# SoundChip.net
KiCad netlist of a schematic drawn in Altium Designer
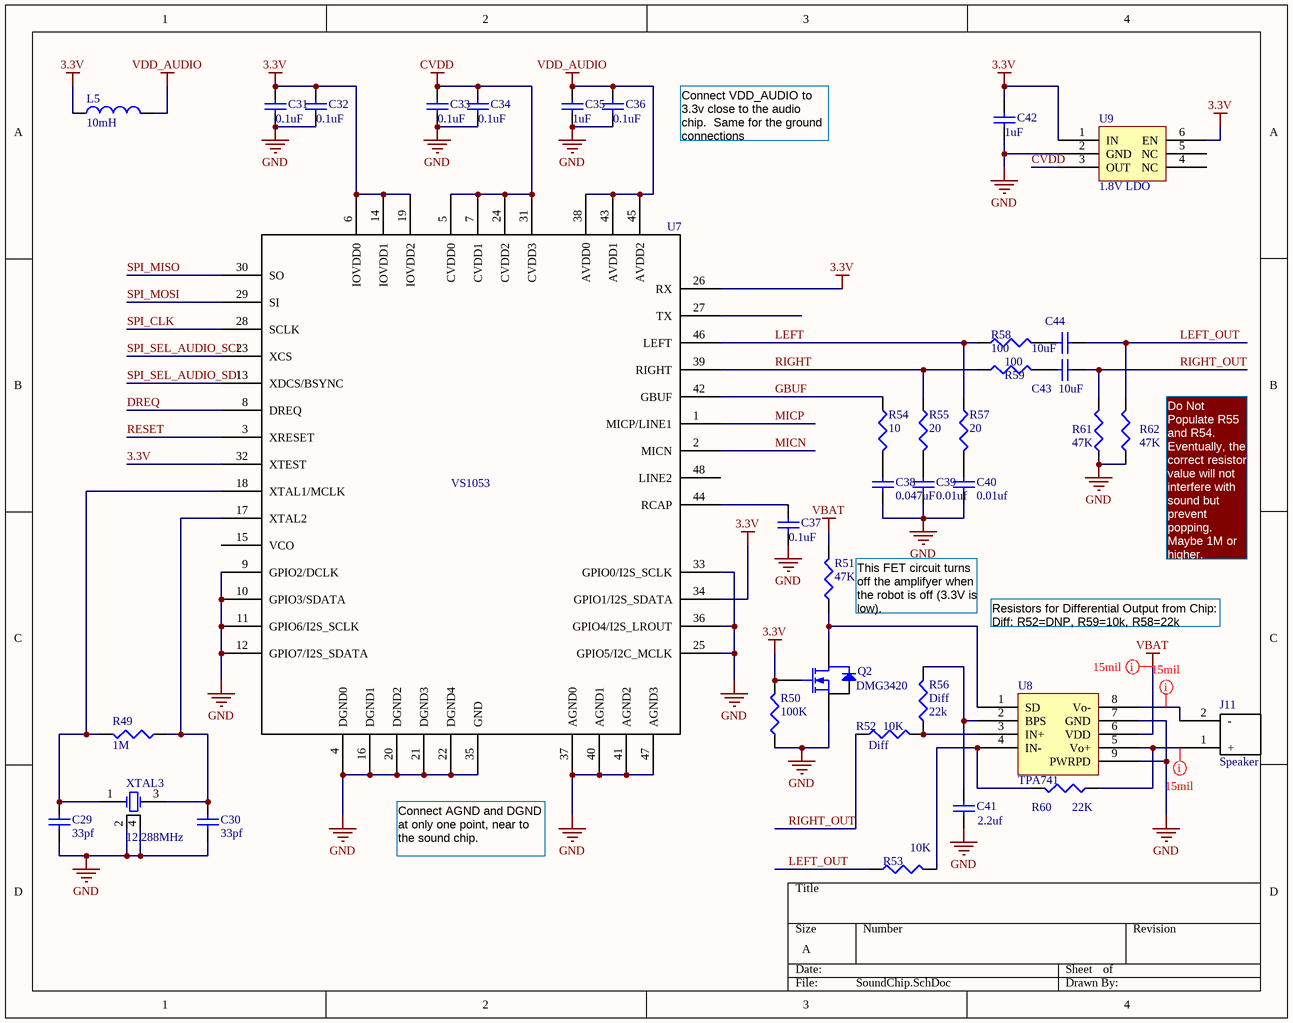
[diagram p0: SoundChip.SchDoc]

(export (version "E")
  (design (tool "Eeschema 10.0.6"))
  (components
    (comp (ref "C29")
      (value "33pf")
      (footprint "CAPC1005L")
      (description "Capacitor (Semiconductor SIM Model)")
      (fields (field (name "Comment") "Cap Semi") (field (name "PUBLISHER") "Altium Limited"))
      (libsource (lib "Miscellaneous Devices") (part "Cap Semi"))
    )
    (comp (ref "C30")
      (value "33pf")
      (footprint "CAPC1005L")
      (description "Capacitor (Semiconductor SIM Model)")
      (fields (field (name "Comment") "Cap Semi") (field (name "PUBLISHER") "Altium Limited"))
      (libsource (lib "Miscellaneous Devices") (part "Cap Semi"))
    )
    (comp (ref "C31")
      (value "0.1uF")
      (footprint "CAPC1005L")
      (description "Capacitor (Semiconductor SIM Model)")
      (fields (field (name "Comment") "Cap Semi") (field (name "PUBLISHER") "Altium Limited"))
      (libsource (lib "Miscellaneous Devices") (part "Cap Semi"))
    )
    (comp (ref "C32")
      (value "0.1uF")
      (footprint "CAPC1005L")
      (description "Capacitor (Semiconductor SIM Model)")
      (fields (field (name "Comment") "Cap Semi") (field (name "PUBLISHER") "Altium Limited"))
      (libsource (lib "Miscellaneous Devices") (part "Cap Semi"))
    )
    (comp (ref "C33")
      (value "0.1uF")
      (footprint "CAPC1005L")
      (description "Capacitor (Semiconductor SIM Model)")
      (fields (field (name "Comment") "Cap Semi") (field (name "PUBLISHER") "Altium Limited"))
      (libsource (lib "Miscellaneous Devices") (part "Cap Semi"))
    )
    (comp (ref "C34")
      (value "0.1uF")
      (footprint "CAPC1005L")
      (description "Capacitor (Semiconductor SIM Model)")
      (fields (field (name "Comment") "Cap Semi") (field (name "PUBLISHER") "Altium Limited"))
      (libsource (lib "Miscellaneous Devices") (part "Cap Semi"))
    )
    (comp (ref "C35")
      (value "1uF")
      (footprint "CAPC1608L")
      (description "Capacitor (Semiconductor SIM Model)")
      (fields (field (name "Comment") "Cap Semi") (field (name "PUBLISHER") "Altium Limited"))
      (libsource (lib "Miscellaneous Devices") (part "Cap Semi"))
    )
    (comp (ref "C36")
      (value "0.1uF")
      (footprint "CAPC1005L")
      (description "Capacitor (Semiconductor SIM Model)")
      (fields (field (name "Comment") "Cap Semi") (field (name "PUBLISHER") "Altium Limited"))
      (libsource (lib "Miscellaneous Devices") (part "Cap Semi"))
    )
    (comp (ref "C37")
      (value "0.1uF")
      (footprint "CAPC1005L")
      (description "Capacitor (Semiconductor SIM Model)")
      (fields (field (name "Comment") "Cap Semi") (field (name "PUBLISHER") "Altium Limited"))
      (libsource (lib "Miscellaneous Devices") (part "Cap Semi"))
    )
    (comp (ref "C38")
      (value "0.047uF")
      (footprint "CAPC1005L")
      (description "Capacitor (Semiconductor SIM Model)")
      (fields (field (name "Comment") "Cap Semi") (field (name "PUBLISHER") "Altium Limited"))
      (libsource (lib "Miscellaneous Devices") (part "Cap Semi"))
    )
    (comp (ref "C39")
      (value "0.01uf")
      (footprint "CAPC1005L")
      (description "Capacitor (Semiconductor SIM Model)")
      (fields (field (name "Comment") "Cap Semi") (field (name "PUBLISHER") "Altium Limited"))
      (libsource (lib "Miscellaneous Devices") (part "Cap Semi"))
    )
    (comp (ref "C40")
      (value "0.01uf")
      (footprint "CAPC1005L")
      (description "Capacitor (Semiconductor SIM Model)")
      (fields (field (name "Comment") "Cap Semi") (field (name "PUBLISHER") "Altium Limited"))
      (libsource (lib "Miscellaneous Devices") (part "Cap Semi"))
    )
    (comp (ref "C41")
      (value "2.2uf")
      (footprint "J1-0603")
      (description "Capacitor (Semiconductor SIM Model)")
      (fields (field (name "Comment") "Cap Semi") (field (name "PUBLISHER") "Altium Limited"))
      (libsource (lib "Miscellaneous Devices") (part "Cap Semi"))
    )
    (comp (ref "C42")
      (value "1uF")
      (footprint "CAPC1608L")
      (description "Capacitor (Semiconductor SIM Model)")
      (fields (field (name "Comment") "Cap Semi") (field (name "PUBLISHER") "Altium Limited"))
      (libsource (lib "Miscellaneous Devices") (part "Cap Semi"))
    )
    (comp (ref "C43")
      (value "10uF")
      (footprint "CAPC1608L")
      (description "Capacitor (Semiconductor SIM Model)")
      (fields (field (name "Comment") "Cap Semi") (field (name "PUBLISHER") "Altium Limited"))
      (libsource (lib "Miscellaneous Devices") (part "Cap Semi"))
    )
    (comp (ref "C44")
      (value "10uF")
      (footprint "CAPC1608L")
      (description "Capacitor (Semiconductor SIM Model)")
      (fields (field (name "Comment") "Cap Semi") (field (name "PUBLISHER") "Altium Limited"))
      (libsource (lib "Miscellaneous Devices") (part "Cap Semi"))
    )
    (comp (ref "J11")
      (value "Speaker")
      (footprint "BatteryConnJST")
      (libsource (lib "mrone") (part "BatteryConnJST"))
    )
    (comp (ref "L5")
      (value "10mH")
      (footprint "INDC2012L")
      (description "Inductor")
      (fields (field (name "PUBLISHER") "Altium Limited"))
      (libsource (lib "Miscellaneous Devices") (part "Inductor"))
    )
    (comp (ref "Q2")
      (value "N-Mosfet")
      (footprint "SOT-23")
      (fields (field (name "MPN") "DMG3420"))
      (libsource (lib "mrone") (part "N-Mosfet"))
    )
    (comp (ref "R49")
      (value "1M")
      (footprint "RESC1608L")
      (description "Resistor")
      (fields (field (name "Comment") "Res3") (field (name "PUBLISHER") "Altium Limited"))
      (libsource (lib "Miscellaneous Devices") (part "Res3"))
    )
    (comp (ref "R50")
      (value "100K")
      (footprint "RESC1608L")
      (description "Resistor")
      (fields (field (name "Comment") "Res3") (field (name "PUBLISHER") "Altium Limited"))
      (libsource (lib "Miscellaneous Devices") (part "Res3"))
    )
    (comp (ref "R51")
      (value "47K")
      (footprint "J1-0603")
      (description "Resistor")
      (fields (field (name "Comment") "Res3") (field (name "PUBLISHER") "Altium Limited"))
      (libsource (lib "Miscellaneous Devices") (part "Res3"))
    )
    (comp (ref "R52")
      (value "Diff")
      (footprint "RESC1608L")
      (description "Resistor")
      (fields (field (name "ALTIUM_VALUE") "10K") (field (name "PUBLISHER") "Altium Limited"))
      (libsource (lib "Miscellaneous Devices") (part "Res3"))
    )
    (comp (ref "R53")
      (value "10K")
      (footprint "RESC1608L")
      (description "Resistor")
      (fields (field (name "Comment") "Res3") (field (name "PUBLISHER") "Altium Limited"))
      (libsource (lib "Miscellaneous Devices") (part "Res3"))
    )
    (comp (ref "R54")
      (value "10")
      (footprint "RESC1608L")
      (description "Resistor")
      (fields (field (name "Comment") "Res3") (field (name "PUBLISHER") "Altium Limited"))
      (libsource (lib "Miscellaneous Devices") (part "Res3"))
    )
    (comp (ref "R55")
      (value "20")
      (footprint "RESC1608L")
      (description "Resistor")
      (fields (field (name "Comment") "Res3") (field (name "PUBLISHER") "Altium Limited"))
      (libsource (lib "Miscellaneous Devices") (part "Res3"))
    )
    (comp (ref "R56")
      (value "Diff")
      (footprint "RESC1608L")
      (description "Resistor")
      (fields (field (name "ALTIUM_VALUE") "22k") (field (name "PUBLISHER") "Altium Limited"))
      (libsource (lib "Miscellaneous Devices") (part "Res3"))
    )
    (comp (ref "R57")
      (value "20")
      (footprint "RESC1608L")
      (description "Resistor")
      (fields (field (name "Comment") "Res3") (field (name "PUBLISHER") "Altium Limited"))
      (libsource (lib "Miscellaneous Devices") (part "Res3"))
    )
    (comp (ref "R58")
      (value "100")
      (footprint "RESC1608L")
      (description "Resistor")
      (fields (field (name "Comment") "Res3") (field (name "PUBLISHER") "Altium Limited"))
      (libsource (lib "Miscellaneous Devices") (part "Res3"))
    )
    (comp (ref "R59")
      (value "100")
      (footprint "RESC1608L")
      (description "Resistor")
      (fields (field (name "Comment") "Res3") (field (name "PUBLISHER") "Altium Limited"))
      (libsource (lib "Miscellaneous Devices") (part "Res3"))
    )
    (comp (ref "R60")
      (value "22K")
      (footprint "RESC1608L")
      (description "Resistor")
      (fields (field (name "Comment") "Res3") (field (name "PUBLISHER") "Altium Limited"))
      (libsource (lib "Miscellaneous Devices") (part "Res3"))
    )
    (comp (ref "R61")
      (value "47K")
      (footprint "RESC1608L")
      (description "Resistor")
      (fields (field (name "Comment") "Res3") (field (name "PUBLISHER") "Altium Limited"))
      (libsource (lib "Miscellaneous Devices") (part "Res3"))
    )
    (comp (ref "R62")
      (value "47K")
      (footprint "RESC1608L")
      (description "Resistor")
      (fields (field (name "Comment") "Res3") (field (name "PUBLISHER") "Altium Limited"))
      (libsource (lib "Miscellaneous Devices") (part "Res3"))
    )
    (comp (ref "U7") (value "VS1053") (footprint "LQFP-48") (libsource (lib "mrone") (part "VS1053")))
    (comp (ref "U8")
      (value "TPA741")
      (footprint "audio amp")
      (libsource (lib "mrone") (part "Audio Amp TPA741"))
    )
    (comp (ref "U9") (value "1.8V LDO") (footprint "WFDFN-6") (libsource (lib "mrone") (part "1.8V_LDO")))
    (comp (ref "XTAL3") (value "12.288MHz") (footprint "CRYSTAL") (libsource (lib "mrone") (part "Crystal")))
  )
  (nets
    (net (code "1") (name "/DREQ") (class "Default")
      (node (ref "U7") (pin "8") (pinfunction "DREQ_8") (pintype "passive"))
    )
    (net (code "2") (name "/GBUF") (class "Default")
      (node (ref "R54") (pin "1") (pinfunction "1_1") (pintype "passive"))
      (node (ref "U7") (pin "42") (pinfunction "GBUF_42") (pintype "passive"))
    )
    (net (code "3") (name "/LEFT") (class "Default")
      (node (ref "R57") (pin "1") (pinfunction "1_1") (pintype "passive"))
      (node (ref "R58") (pin "1") (pinfunction "1_1") (pintype "passive"))
      (node (ref "U7") (pin "46") (pinfunction "LEFT_46") (pintype "passive"))
    )
    (net (code "4") (name "/LEFT_OUT") (class "Default")
      (node (ref "C44") (pin "1") (pinfunction "1_1") (pintype "passive"))
      (node (ref "R53") (pin "1") (pinfunction "1_1") (pintype "passive"))
      (node (ref "R62") (pin "2") (pinfunction "2_2") (pintype "passive"))
    )
    (net (code "5") (name "/MICN") (class "Default")
      (node (ref "U7") (pin "2") (pinfunction "MICN_2") (pintype "passive"))
    )
    (net (code "6") (name "/MICP") (class "Default")
      (node (ref "U7") (pin "1") (pinfunction "MICP/LINE1_1") (pintype "passive"))
    )
    (net (code "7") (name "/RESET") (class "Default")
      (node (ref "U7") (pin "3") (pinfunction "XRESET_3") (pintype "passive"))
    )
    (net (code "8") (name "/RIGHT") (class "Default")
      (node (ref "R55") (pin "1") (pinfunction "1_1") (pintype "passive"))
      (node (ref "R59") (pin "1") (pinfunction "1_1") (pintype "passive"))
      (node (ref "U7") (pin "39") (pinfunction "RIGHT_39") (pintype "passive"))
    )
    (net (code "9") (name "/RIGHT_OUT") (class "Default")
      (node (ref "C43") (pin "1") (pinfunction "1_1") (pintype "passive"))
      (node (ref "R52") (pin "1") (pinfunction "1_1") (pintype "passive"))
      (node (ref "R61") (pin "2") (pinfunction "2_2") (pintype "passive"))
    )
    (net (code "10") (name "/SPI_CLK") (class "Default")
      (node (ref "U7") (pin "28") (pinfunction "SCLK_28") (pintype "passive"))
    )
    (net (code "11") (name "/SPI_MISO") (class "Default")
      (node (ref "U7") (pin "30") (pinfunction "SO_30") (pintype "passive"))
    )
    (net (code "12") (name "/SPI_MOSI") (class "Default")
      (node (ref "U7") (pin "29") (pinfunction "SI_29") (pintype "passive"))
    )
    (net (code "13") (name "/SPI_SEL_AUDIO_SCI") (class "Default")
      (node (ref "U7") (pin "23") (pinfunction "XCS_23") (pintype "passive"))
    )
    (net (code "14") (name "/SPI_SEL_AUDIO_SDI") (class "Default")
      (node (ref "U7") (pin "13") (pinfunction "XDCS/BSYNC_13") (pintype "passive"))
    )
    (net (code "15") (name "3.3V") (class "Default")
      (node (ref "C31") (pin "2") (pinfunction "2_2") (pintype "passive"))
      (node (ref "C32") (pin "2") (pinfunction "2_2") (pintype "passive"))
      (node (ref "C42") (pin "1") (pinfunction "1_1") (pintype "passive"))
      (node (ref "L5") (pin "2") (pinfunction "2_2") (pintype "passive"))
      (node (ref "Q2") (pin "1") (pinfunction "G_1") (pintype "passive"))
      (node (ref "R50") (pin "2") (pinfunction "2_2") (pintype "passive"))
      (node (ref "U7") (pin "14") (pinfunction "IOVDD1_14") (pintype "passive"))
      (node (ref "U7") (pin "19") (pinfunction "IOVDD2_19") (pintype "passive"))
      (node (ref "U7") (pin "26") (pinfunction "RX_26") (pintype "passive"))
      (node (ref "U7") (pin "32") (pinfunction "XTEST_32") (pintype "passive"))
      (node (ref "U7") (pin "34") (pinfunction "GPIO1/I2S_SDATA_34") (pintype "passive"))
      (node (ref "U7") (pin "6") (pinfunction "IOVDD0_6") (pintype "passive"))
      (node (ref "U9") (pin "1") (pinfunction "IN_1") (pintype "passive"))
      (node (ref "U9") (pin "6") (pinfunction "EN_6") (pintype "passive"))
    )
    (net (code "16") (name "CVDD") (class "Default")
      (node (ref "C33") (pin "2") (pinfunction "2_2") (pintype "passive"))
      (node (ref "C34") (pin "2") (pinfunction "2_2") (pintype "passive"))
      (node (ref "U7") (pin "24") (pinfunction "CVDD2_24") (pintype "passive"))
      (node (ref "U7") (pin "31") (pinfunction "CVDD3_31") (pintype "passive"))
      (node (ref "U7") (pin "5") (pinfunction "CVDD0_5") (pintype "passive"))
      (node (ref "U7") (pin "7") (pinfunction "CVDD1_7") (pintype "passive"))
      (node (ref "U9") (pin "3") (pinfunction "OUT_3") (pintype "passive"))
    )
    (net (code "17") (name "GND") (class "Default")
      (node (ref "C29") (pin "2") (pinfunction "2_2") (pintype "passive"))
      (node (ref "C30") (pin "2") (pinfunction "2_2") (pintype "passive"))
      (node (ref "C31") (pin "1") (pinfunction "1_1") (pintype "passive"))
      (node (ref "C32") (pin "1") (pinfunction "1_1") (pintype "passive"))
      (node (ref "C33") (pin "1") (pinfunction "1_1") (pintype "passive"))
      (node (ref "C34") (pin "1") (pinfunction "1_1") (pintype "passive"))
      (node (ref "C35") (pin "2") (pinfunction "2_2") (pintype "passive"))
      (node (ref "C36") (pin "1") (pinfunction "1_1") (pintype "passive"))
      (node (ref "C37") (pin "1") (pinfunction "1_1") (pintype "passive"))
      (node (ref "C38") (pin "2") (pinfunction "2_2") (pintype "passive"))
      (node (ref "C39") (pin "2") (pinfunction "2_2") (pintype "passive"))
      (node (ref "C40") (pin "2") (pinfunction "2_2") (pintype "passive"))
      (node (ref "C41") (pin "1") (pinfunction "1_1") (pintype "passive"))
      (node (ref "C42") (pin "2") (pinfunction "2_2") (pintype "passive"))
      (node (ref "Q2") (pin "2") (pinfunction "S_2") (pintype "passive"))
      (node (ref "R50") (pin "1") (pinfunction "1_1") (pintype "passive"))
      (node (ref "R61") (pin "1") (pinfunction "1_1") (pintype "passive"))
      (node (ref "R62") (pin "1") (pinfunction "1_1") (pintype "passive"))
      (node (ref "U7") (pin "10") (pinfunction "GPIO3/SDATA_10") (pintype "passive"))
      (node (ref "U7") (pin "11") (pinfunction "GPIO6/I2S_SCLK_11") (pintype "passive"))
      (node (ref "U7") (pin "12") (pinfunction "GPIO7/I2S_SDATA_12") (pintype "passive"))
      (node (ref "U7") (pin "16") (pinfunction "DGND1_16") (pintype "passive"))
      (node (ref "U7") (pin "20") (pinfunction "DGND2_20") (pintype "passive"))
      (node (ref "U7") (pin "21") (pinfunction "DGND3_21") (pintype "passive"))
      (node (ref "U7") (pin "22") (pinfunction "DGND4_22") (pintype "passive"))
      (node (ref "U7") (pin "25") (pinfunction "GPIO5/I2C_MCLK_25") (pintype "passive"))
      (node (ref "U7") (pin "33") (pinfunction "GPIO0/I2S_SCLK_33") (pintype "passive"))
      (node (ref "U7") (pin "35") (pinfunction "GND_35") (pintype "passive"))
      (node (ref "U7") (pin "36") (pinfunction "GPIO4/I2S_LROUT_36") (pintype "passive"))
      (node (ref "U7") (pin "37") (pinfunction "AGND0_37") (pintype "passive"))
      (node (ref "U7") (pin "4") (pinfunction "DGND0_4") (pintype "passive"))
      (node (ref "U7") (pin "40") (pinfunction "AGND1_40") (pintype "passive"))
      (node (ref "U7") (pin "41") (pinfunction "AGND2_41") (pintype "passive"))
      (node (ref "U7") (pin "47") (pinfunction "AGND3_47") (pintype "passive"))
      (node (ref "U7") (pin "9") (pinfunction "GPIO2/DCLK_9") (pintype "passive"))
      (node (ref "U8") (pin "7") (pinfunction "GND_7") (pintype "passive"))
      (node (ref "U8") (pin "9") (pinfunction "PWRPD_9") (pintype "passive"))
      (node (ref "U9") (pin "2") (pinfunction "GND_2") (pintype "passive"))
      (node (ref "XTAL3") (pin "2") (pinfunction "GND_2") (pintype "passive"))
      (node (ref "XTAL3") (pin "4") (pinfunction "GND_4") (pintype "passive"))
    )
    (net (code "18") (name "Net-(C38-Pad1)") (class "Default")
      (node (ref "C38") (pin "1") (pinfunction "1_1") (pintype "passive"))
      (node (ref "R54") (pin "2") (pinfunction "2_2") (pintype "passive"))
    )
    (net (code "19") (name "Net-(C39-Pad1)") (class "Default")
      (node (ref "C39") (pin "1") (pinfunction "1_1") (pintype "passive"))
      (node (ref "R55") (pin "2") (pinfunction "2_2") (pintype "passive"))
    )
    (net (code "20") (name "Net-(C40-Pad1)") (class "Default")
      (node (ref "C40") (pin "1") (pinfunction "1_1") (pintype "passive"))
      (node (ref "R57") (pin "2") (pinfunction "2_2") (pintype "passive"))
    )
    (net (code "21") (name "Net-(C43-Pad2)") (class "Default")
      (node (ref "C43") (pin "2") (pinfunction "2_2") (pintype "passive"))
      (node (ref "R59") (pin "2") (pinfunction "2_2") (pintype "passive"))
    )
    (net (code "22") (name "Net-(C44-Pad2)") (class "Default")
      (node (ref "C44") (pin "2") (pinfunction "2_2") (pintype "passive"))
      (node (ref "R58") (pin "2") (pinfunction "2_2") (pintype "passive"))
    )
    (net (code "23") (name "Net-(J11-+)") (class "Default")
      (node (ref "J11") (pin "1") (pinfunction "+_1") (pintype "passive"))
      (node (ref "R60") (pin "1") (pinfunction "1_1") (pintype "passive"))
      (node (ref "U8") (pin "5") (pinfunction "Vo+_5") (pintype "passive"))
    )
    (net (code "24") (name "Net-(J11--)") (class "Default")
      (node (ref "J11") (pin "2") (pinfunction "-_2") (pintype "passive"))
      (node (ref "U8") (pin "8") (pinfunction "Vo-_8") (pintype "passive"))
    )
    (net (code "25") (name "Net-(Q2-D)") (class "Default")
      (node (ref "Q2") (pin "3") (pinfunction "D_3") (pintype "passive"))
      (node (ref "R51") (pin "1") (pinfunction "1_1") (pintype "passive"))
      (node (ref "U8") (pin "1") (pinfunction "SD_1") (pintype "passive"))
    )
    (net (code "26") (name "Net-(U7-RCAP)") (class "Default")
      (node (ref "C37") (pin "2") (pinfunction "2_2") (pintype "passive"))
      (node (ref "U7") (pin "44") (pinfunction "RCAP_44") (pintype "passive"))
    )
    (net (code "27") (name "Net-(U7-XTAL1{slash}MCLK)") (class "Default")
      (node (ref "C29") (pin "1") (pinfunction "1_1") (pintype "passive"))
      (node (ref "R49") (pin "2") (pinfunction "2_2") (pintype "passive"))
      (node (ref "U7") (pin "18") (pinfunction "XTAL1/MCLK_18") (pintype "passive"))
      (node (ref "XTAL3") (pin "1") (pinfunction "OSC1_1") (pintype "passive"))
    )
    (net (code "28") (name "Net-(U7-XTAL2)") (class "Default")
      (node (ref "C30") (pin "1") (pinfunction "1_1") (pintype "passive"))
      (node (ref "R49") (pin "1") (pinfunction "1_1") (pintype "passive"))
      (node (ref "U7") (pin "17") (pinfunction "XTAL2_17") (pintype "passive"))
      (node (ref "XTAL3") (pin "3") (pinfunction "OSC2_3") (pintype "passive"))
    )
    (net (code "29") (name "Net-(U8-BPS)") (class "Default")
      (node (ref "C41") (pin "2") (pinfunction "2_2") (pintype "passive"))
      (node (ref "R56") (pin "2") (pinfunction "2_2") (pintype "passive"))
      (node (ref "U8") (pin "2") (pinfunction "BPS_2") (pintype "passive"))
    )
    (net (code "30") (name "Net-(U8-IN+)") (class "Default")
      (node (ref "R52") (pin "2") (pinfunction "2_2") (pintype "passive"))
      (node (ref "R56") (pin "1") (pinfunction "1_1") (pintype "passive"))
      (node (ref "U8") (pin "3") (pinfunction "IN+_3") (pintype "passive"))
    )
    (net (code "31") (name "Net-(U8-IN-)") (class "Default")
      (node (ref "R53") (pin "2") (pinfunction "2_2") (pintype "passive"))
      (node (ref "R60") (pin "2") (pinfunction "2_2") (pintype "passive"))
      (node (ref "U8") (pin "4") (pinfunction "IN-_4") (pintype "passive"))
    )
    (net (code "32") (name "VBAT") (class "Default")
      (node (ref "R51") (pin "2") (pinfunction "2_2") (pintype "passive"))
      (node (ref "U8") (pin "6") (pinfunction "VDD_6") (pintype "passive"))
    )
    (net (code "33") (name "VDD_AUDIO") (class "Default")
      (node (ref "C35") (pin "1") (pinfunction "1_1") (pintype "passive"))
      (node (ref "C36") (pin "2") (pinfunction "2_2") (pintype "passive"))
      (node (ref "L5") (pin "1") (pinfunction "1_1") (pintype "passive"))
      (node (ref "U7") (pin "38") (pinfunction "AVDD0_38") (pintype "passive"))
      (node (ref "U7") (pin "43") (pinfunction "AVDD1_43") (pintype "passive"))
      (node (ref "U7") (pin "45") (pinfunction "AVDD2_45") (pintype "passive"))
    )
    (net (code "34") (name "unconnected-(U7-LINE2-Pad48)") (class "Default")
      (node (ref "U7") (pin "48") (pinfunction "LINE2_48") (pintype "passive"))
    )
    (net (code "35") (name "unconnected-(U7-TX-Pad27)") (class "Default")
      (node (ref "U7") (pin "27") (pinfunction "TX_27") (pintype "passive"))
    )
    (net (code "36") (name "unconnected-(U7-VCO-Pad15)") (class "Default")
      (node (ref "U7") (pin "15") (pinfunction "VCO_15") (pintype "passive"))
    )
    (net (code "37") (name "unconnected-(U9-NC-Pad4)") (class "Default")
      (node (ref "U9") (pin "4") (pinfunction "NC_4") (pintype "passive"))
    )
    (net (code "38") (name "unconnected-(U9-NC-Pad5)") (class "Default")
      (node (ref "U9") (pin "5") (pinfunction "NC_5") (pintype "passive"))
    )
  )
)
